# pblcompleted.net
KiCad netlist of a schematic drawn in EAGLE
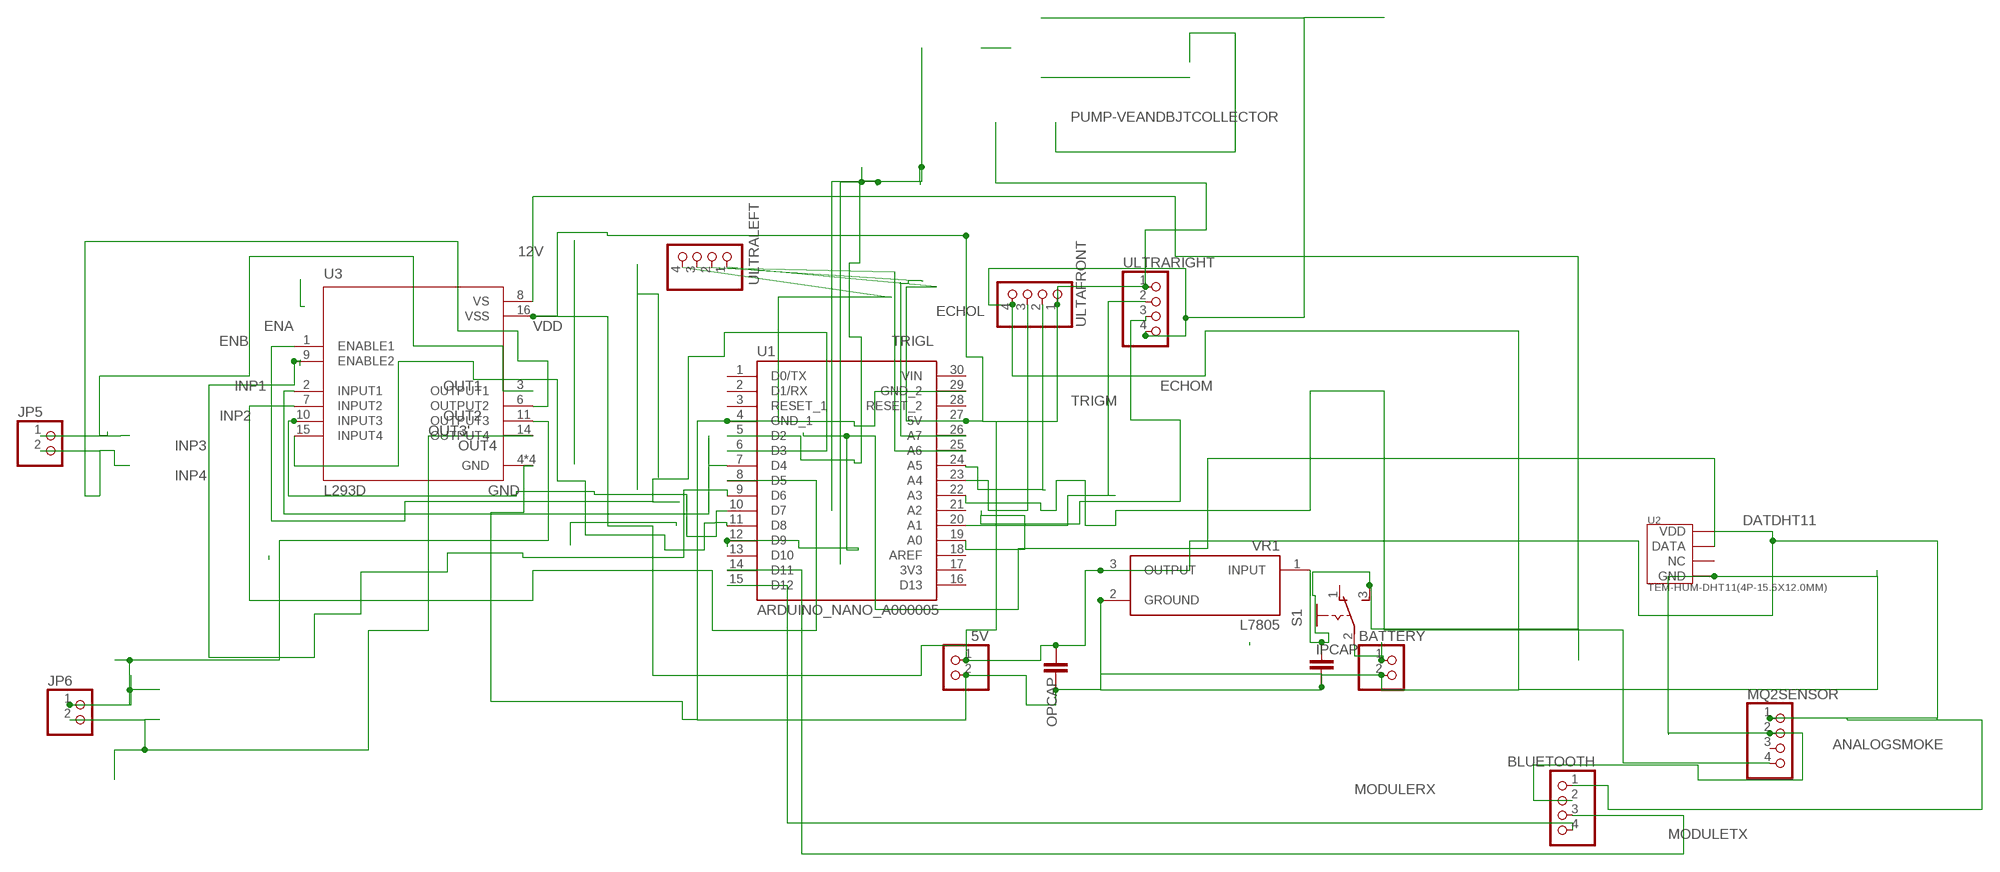
[diagram p0: schematic, sheet 1]

(export (version "E")
  (design (tool "Eeschema 10.0.6"))
  (components
    (comp (ref "5V")
      (value "PINHD-1X2")
      (footprint "eagle-import:1X02")
      (libsource (lib "eagle-import") (part "PINHD-1X2"))
    )
    (comp (ref "BATTERY")
      (value "PINHD-1X2")
      (footprint "eagle-import:1X02")
      (libsource (lib "eagle-import") (part "PINHD-1X2"))
    )
    (comp (ref "BLUETOOTH")
      (value "PINHD-1X4")
      (footprint "eagle-import:1X04")
      (libsource (lib "eagle-import") (part "PINHD-1X4"))
    )
    (comp (ref "IPCAP")
      (value "C2,5-3")
      (footprint "eagle-import:C2.5-3")
      (libsource (lib "eagle-import") (part "C2,5-3"))
    )
    (comp (ref "JP5")
      (value "PINHD-1X2")
      (footprint "eagle-import:1X02")
      (libsource (lib "eagle-import") (part "PINHD-1X2"))
    )
    (comp (ref "JP6")
      (value "PINHD-1X2")
      (footprint "eagle-import:1X02")
      (libsource (lib "eagle-import") (part "PINHD-1X2"))
    )
    (comp (ref "MQ2SENSOR")
      (value "PINHD-1X4")
      (footprint "eagle-import:1X04")
      (libsource (lib "eagle-import") (part "PINHD-1X4"))
    )
    (comp (ref "OPCAP")
      (value "C2,5-3")
      (footprint "eagle-import:C2.5-3")
      (libsource (lib "eagle-import") (part "C2,5-3"))
    )
    (comp (ref "S1")
      (value "255SB")
      (footprint "eagle-import:255SB")
      (libsource (lib "eagle-import") (part "255SB"))
    )
    (comp (ref "U1")
      (value "ARDUINO_NANO_A000005")
      (footprint "eagle-import:MODULE_ARDUINO_NANO_A000005")
      (fields (field (name "MF") "Arduino") (field (name "MP") "ARDUINO NANO A000005"))
      (libsource (lib "eagle-import") (part "ARDUINO_NANO_A000005"))
    )
    (comp (ref "U2")
      (value "TEM-HUM-DHT11(4P-15.5X12.0MM)")
      (footprint "eagle-import:SNR4-2.54-15.5X12.0X5.5MM")
      (fields (field (name "MF") "aosong") (field (name "MP") "DHT11"))
      (libsource (lib "eagle-import") (part "TEM-HUM-DHT11(4P-15.5X12.0MM)"))
    )
    (comp (ref "U3")
      (value "L293D")
      (footprint "eagle-import:DIP880W50P254L2000H510Q16")
      (fields (field (name "MF") "STMicroelectronics"))
      (libsource (lib "eagle-import") (part "L293D"))
    )
    (comp (ref "ULTAFRONT")
      (value "PINHD-1X4")
      (footprint "eagle-import:1X04")
      (libsource (lib "eagle-import") (part "PINHD-1X4"))
    )
    (comp (ref "ULTRALEFT")
      (value "PINHD-1X4")
      (footprint "eagle-import:1X04")
      (libsource (lib "eagle-import") (part "PINHD-1X4"))
    )
    (comp (ref "ULTRARIGHT")
      (value "PINHD-1X4")
      (footprint "eagle-import:1X04")
      (libsource (lib "eagle-import") (part "PINHD-1X4"))
    )
    (comp (ref "VR1")
      (value "L7805")
      (footprint "eagle-import:TO255P1020X450X2000-3")
      (fields (field (name "MF") "STMicroelectronics"))
      (libsource (lib "eagle-import") (part "L7805"))
    )
  )
  (nets
    (net (code "1") (name "/3V3") (class "Default")
      (node (ref "U1") (pin "17") (pinfunction "3V3_17") (pintype "power_in"))
    )
    (net (code "2") (name "/12V") (class "Default")
      (node (ref "IPCAP") (pin "1") (pinfunction "1_1") (pintype "passive"))
      (node (ref "S1") (pin "3") (pinfunction "S_3") (pintype "passive"))
      (node (ref "U3") (pin "8") (pinfunction "VS_8") (pintype "power_in"))
      (node (ref "VR1") (pin "1") (pinfunction "INPUT_1") (pintype "input"))
    )
    (net (code "3") (name "/ANALOGSMOKE") (class "Default")
      (node (ref "MQ2SENSOR") (pin "4") (pinfunction "4_4") (pintype "passive"))
      (node (ref "U1") (pin "22") (pinfunction "A3_22") (pintype "input"))
    )
    (net (code "4") (name "/DATDHT11") (class "Default")
      (node (ref "U1") (pin "12") (pinfunction "D9_12") (pintype "bidirectional"))
      (node (ref "U2") (pin "2") (pinfunction "DATA_2") (pintype "bidirectional"))
    )
    (net (code "5") (name "/ECHOL") (class "Default")
      (node (ref "U1") (pin "25") (pinfunction "A6_25") (pintype "input"))
      (node (ref "ULTRALEFT") (pin "3") (pinfunction "3_3") (pintype "passive"))
    )
    (net (code "6") (name "/ECHOM") (class "Default")
      (node (ref "U1") (pin "23") (pinfunction "A4_23") (pintype "input"))
      (node (ref "ULTAFRONT") (pin "3") (pinfunction "3_3") (pintype "passive"))
    )
    (net (code "7") (name "/ENA") (class "Default")
      (node (ref "U1") (pin "6") (pinfunction "D3_6") (pintype "bidirectional"))
      (node (ref "U3") (pin "1") (pinfunction "ENABLE1_1") (pintype "input"))
    )
    (net (code "8") (name "/ENB") (class "Default")
      (node (ref "U1") (pin "9") (pinfunction "D6_9") (pintype "bidirectional"))
      (node (ref "U3") (pin "9") (pinfunction "ENABLE2_9") (pintype "input"))
    )
    (net (code "9") (name "/GND") (class "Default")
      (node (ref "5V") (pin "2") (pinfunction "2_2") (pintype "passive"))
      (node (ref "BATTERY") (pin "2") (pinfunction "2_2") (pintype "passive"))
      (node (ref "BLUETOOTH") (pin "2") (pinfunction "2_2") (pintype "passive"))
      (node (ref "IPCAP") (pin "2") (pinfunction "2_2") (pintype "passive"))
      (node (ref "MQ2SENSOR") (pin "2") (pinfunction "2_2") (pintype "passive"))
      (node (ref "OPCAP") (pin "1") (pinfunction "1_1") (pintype "passive"))
      (node (ref "U1") (pin "29") (pinfunction "GND_2_29") (pintype "power_in"))
      (node (ref "U1") (pin "4") (pinfunction "GND_1_4") (pintype "power_in"))
      (node (ref "U2") (pin "4") (pinfunction "GND_4") (pintype "power_in"))
      (node (ref "U3") (pin "12") (pinfunction "GND_12") (pintype "power_in"))
      (node (ref "U3") (pin "13") (pinfunction "GND_13") (pintype "power_in"))
      (node (ref "U3") (pin "4") (pinfunction "GND_4") (pintype "power_in"))
      (node (ref "U3") (pin "5") (pinfunction "GND_5") (pintype "power_in"))
      (node (ref "ULTAFRONT") (pin "4") (pinfunction "4_4") (pintype "passive"))
      (node (ref "ULTRALEFT") (pin "4") (pinfunction "4_4") (pintype "passive"))
      (node (ref "ULTRARIGHT") (pin "4") (pinfunction "4_4") (pintype "passive"))
      (node (ref "VR1") (pin "2") (pinfunction "GROUND_2") (pintype "power_in"))
    )
    (net (code "10") (name "/INP1") (class "Default")
      (node (ref "U1") (pin "7") (pinfunction "D4_7") (pintype "bidirectional"))
      (node (ref "U3") (pin "2") (pinfunction "INPUT1_2") (pintype "input"))
    )
    (net (code "11") (name "/INP2") (class "Default")
      (node (ref "U1") (pin "8") (pinfunction "D5_8") (pintype "bidirectional"))
      (node (ref "U3") (pin "7") (pinfunction "INPUT2_7") (pintype "input"))
    )
    (net (code "12") (name "/INP3") (class "Default")
      (node (ref "U1") (pin "10") (pinfunction "D7_10") (pintype "bidirectional"))
      (node (ref "U3") (pin "10") (pinfunction "INPUT3_10") (pintype "input"))
    )
    (net (code "13") (name "/INP4") (class "Default")
      (node (ref "U1") (pin "11") (pinfunction "D8_11") (pintype "bidirectional"))
      (node (ref "U3") (pin "15") (pinfunction "INPUT4_15") (pintype "input"))
    )
    (net (code "14") (name "/MODULERX") (class "Default")
      (node (ref "BLUETOOTH") (pin "4") (pinfunction "4_4") (pintype "passive"))
      (node (ref "U1") (pin "15") (pinfunction "D12_15") (pintype "bidirectional"))
    )
    (net (code "15") (name "/MODULETX") (class "Default")
      (node (ref "BLUETOOTH") (pin "3") (pinfunction "3_3") (pintype "passive"))
      (node (ref "U1") (pin "14") (pinfunction "D11_14") (pintype "bidirectional"))
    )
    (net (code "16") (name "/OUT1") (class "Default")
      (node (ref "JP5") (pin "1") (pinfunction "1_1") (pintype "passive"))
      (node (ref "U3") (pin "3") (pinfunction "OUTPUT1_3") (pintype "output"))
    )
    (net (code "17") (name "/OUT2") (class "Default")
      (node (ref "JP5") (pin "2") (pinfunction "2_2") (pintype "passive"))
      (node (ref "U3") (pin "6") (pinfunction "OUTPUT2_6") (pintype "output"))
    )
    (net (code "18") (name "/OUT3'") (class "Default")
      (node (ref "JP6") (pin "1") (pinfunction "1_1") (pintype "passive"))
      (node (ref "U3") (pin "11") (pinfunction "OUTPUT3_11") (pintype "output"))
    )
    (net (code "19") (name "/OUT4") (class "Default")
      (node (ref "JP6") (pin "2") (pinfunction "2_2") (pintype "passive"))
      (node (ref "U3") (pin "14") (pinfunction "OUTPUT4_14") (pintype "output"))
    )
    (net (code "21") (name "/TRIGL") (class "Default")
      (node (ref "U1") (pin "26") (pinfunction "A7_26") (pintype "input"))
      (node (ref "ULTRALEFT") (pin "2") (pinfunction "2_2") (pintype "passive"))
    )
    (net (code "22") (name "/TRIGM") (class "Default")
      (node (ref "U1") (pin "24") (pinfunction "A5_24") (pintype "input"))
      (node (ref "ULTAFRONT") (pin "2") (pinfunction "2_2") (pintype "passive"))
    )
    (net (code "23") (name "/VDD") (class "Default")
      (node (ref "5V") (pin "1") (pinfunction "1_1") (pintype "passive"))
      (node (ref "BLUETOOTH") (pin "1") (pinfunction "1_1") (pintype "passive"))
      (node (ref "MQ2SENSOR") (pin "1") (pinfunction "1_1") (pintype "passive"))
      (node (ref "OPCAP") (pin "2") (pinfunction "2_2") (pintype "passive"))
      (node (ref "U1") (pin "27") (pinfunction "5V_27") (pintype "power_in"))
      (node (ref "U2") (pin "1") (pinfunction "VDD_1") (pintype "power_in"))
      (node (ref "U3") (pin "16") (pinfunction "VSS_16") (pintype "power_in"))
      (node (ref "ULTAFRONT") (pin "1") (pinfunction "1_1") (pintype "passive"))
      (node (ref "ULTRALEFT") (pin "1") (pinfunction "1_1") (pintype "passive"))
      (node (ref "ULTRARIGHT") (pin "1") (pinfunction "1_1") (pintype "passive"))
      (node (ref "VR1") (pin "3") (pinfunction "OUTPUT_3") (pintype "output"))
    )
    (net (code "24") (name "/VIN") (class "Default")
      (node (ref "U1") (pin "30") (pinfunction "VIN_30") (pintype "power_in"))
    )
    (net (code "25") (name "Net-(S1-P)") (class "Default")
      (node (ref "BATTERY") (pin "1") (pinfunction "1_1") (pintype "passive"))
      (node (ref "S1") (pin "2") (pinfunction "P_2") (pintype "passive"))
    )
    (net (code "26") (name "Net-(U1-A0)") (class "Default")
      (node (ref "U1") (pin "19") (pinfunction "A0_19") (pintype "input"))
      (node (ref "ULTRARIGHT") (pin "3") (pinfunction "3_3") (pintype "passive"))
    )
    (net (code "27") (name "Net-(U1-A1)") (class "Default")
      (node (ref "U1") (pin "20") (pinfunction "A1_20") (pintype "input"))
      (node (ref "ULTRARIGHT") (pin "2") (pinfunction "2_2") (pintype "passive"))
    )
    (net (code "28") (name "unconnected-(MQ2SENSOR-Pad3)") (class "Default")
      (node (ref "MQ2SENSOR") (pin "3") (pinfunction "3_3") (pintype "passive"))
    )
    (net (code "29") (name "unconnected-(S1-O-Pad1)") (class "Default")
      (node (ref "S1") (pin "1") (pinfunction "O_1") (pintype "passive"))
    )
    (net (code "30") (name "unconnected-(U1-A2-Pad21)") (class "Default")
      (node (ref "U1") (pin "21") (pinfunction "A2_21") (pintype "input"))
    )
    (net (code "31") (name "unconnected-(U1-AREF-Pad18)") (class "Default")
      (node (ref "U1") (pin "18") (pinfunction "AREF_18") (pintype "input"))
    )
    (net (code "32") (name "unconnected-(U1-D0{slash}TX-Pad1)") (class "Default")
      (node (ref "U1") (pin "1") (pinfunction "D0/TX_1") (pintype "bidirectional"))
    )
    (net (code "33") (name "unconnected-(U1-D1{slash}RX-Pad2)") (class "Default")
      (node (ref "U1") (pin "2") (pinfunction "D1/RX_2") (pintype "bidirectional"))
    )
    (net (code "34") (name "unconnected-(U1-D2-Pad5)") (class "Default")
      (node (ref "U1") (pin "5") (pinfunction "D2_5") (pintype "bidirectional"))
    )
    (net (code "35") (name "unconnected-(U1-D10-Pad13)") (class "Default")
      (node (ref "U1") (pin "13") (pinfunction "D10_13") (pintype "bidirectional"))
    )
    (net (code "36") (name "unconnected-(U1-D13-Pad16)") (class "Default")
      (node (ref "U1") (pin "16") (pinfunction "D13_16") (pintype "bidirectional"))
    )
    (net (code "37") (name "unconnected-(U1-RESET_1-Pad3)") (class "Default")
      (node (ref "U1") (pin "3") (pinfunction "RESET_1_3") (pintype "input"))
    )
    (net (code "38") (name "unconnected-(U1-RESET_2-Pad28)") (class "Default")
      (node (ref "U1") (pin "28") (pinfunction "RESET_2_28") (pintype "input"))
    )
    (net (code "39") (name "unconnected-(U2-NC-Pad3)") (class "Default")
      (node (ref "U2") (pin "3") (pinfunction "NC_3") (pintype "no_connect"))
    )
  )
)
